# MB1-USB-r1_0.net
KiCad netlist of a schematic drawn in Altium Designer
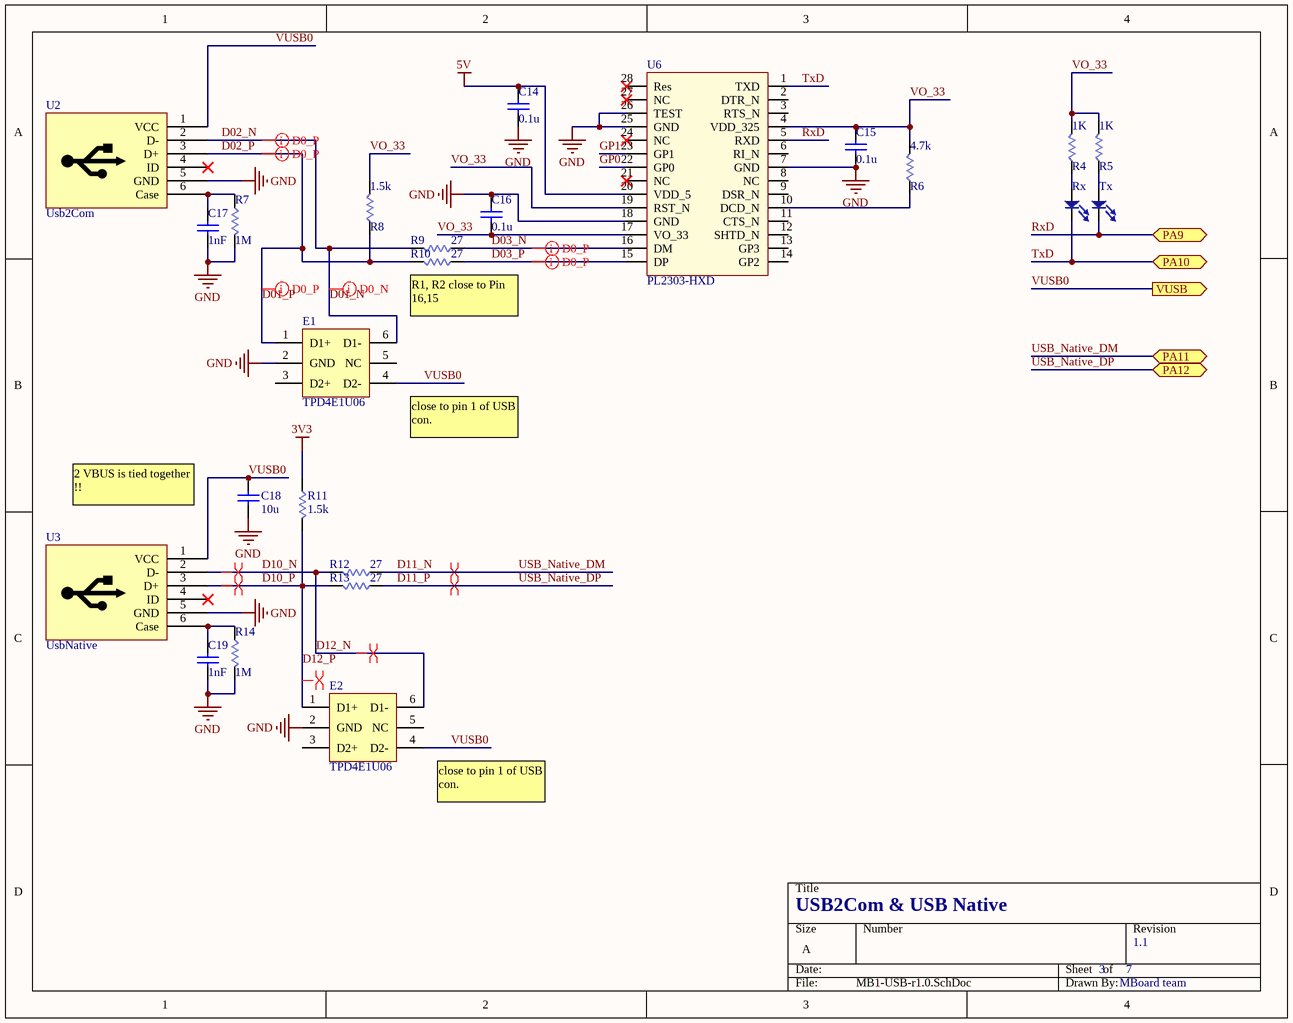
[diagram p0: MB1-USB-r1.0.SchDoc]

(export (version "E")
  (design (tool "Eeschema 10.0.6"))
  (components
    (comp (ref "C14")
      (value "0.1u")
      (footprint "SM_0805_C_CERAMIC")
      (description "Non-polarity ceramic capacitor")
      (fields (field (name "Comment") "CAP Ceramic") (field (name "PUBLISHER") "Altium Limited"))
      (libsource (lib "HLib_schematic_lib") (part "CAP Ceramic"))
    )
    (comp (ref "C15")
      (value "0.1u")
      (footprint "SM_0805_C_CERAMIC")
      (description "Non-polarity ceramic capacitor")
      (fields (field (name "Comment") "CAP Ceramic") (field (name "PUBLISHER") "Altium Limited"))
      (libsource (lib "HLib_schematic_lib") (part "CAP Ceramic"))
    )
    (comp (ref "C16")
      (value "0.1u")
      (footprint "SM_0805_C_CERAMIC")
      (description "Non-polarity ceramic capacitor")
      (fields (field (name "Comment") "CAP Ceramic") (field (name "PUBLISHER") "Altium Limited"))
      (libsource (lib "HLib_schematic_lib") (part "CAP Ceramic"))
    )
    (comp (ref "C17")
      (value "1nF")
      (footprint "SM_0805_C_CERAMIC")
      (description "Non-polarity ceramic capacitor")
      (fields (field (name "Comment") "CAP Ceramic") (field (name "PUBLISHER") "Altium Limited"))
      (libsource (lib "HLib_schematic_lib") (part "CAP Ceramic"))
    )
    (comp (ref "C18")
      (value "10u")
      (footprint "SM_0805_C_CERAMIC")
      (description "Non-polarity ceramic capacitor")
      (fields (field (name "Comment") "CAP Ceramic") (field (name "PUBLISHER") "Altium Limited"))
      (libsource (lib "HLib_schematic_lib") (part "CAP Ceramic"))
    )
    (comp (ref "C19")
      (value "1nF")
      (footprint "SM_0805_C_CERAMIC")
      (description "Non-polarity ceramic capacitor")
      (fields (field (name "Comment") "CAP Ceramic") (field (name "PUBLISHER") "Altium Limited"))
      (libsource (lib "HLib_schematic_lib") (part "CAP Ceramic"))
    )
    (comp (ref "E1") (value "TPD4E1U06") (footprint "SC70-6") (libsource (lib "MyLib") (part "TPD4E1U06")))
    (comp (ref "E2") (value "TPD4E1U06") (footprint "SC70-6") (libsource (lib "MyLib") (part "TPD4E1U06")))
    (comp (ref "R4")
      (value "1K")
      (footprint "SM_0805_R")
      (description "Resistor")
      (fields (field (name "PUBLISHER") "Altium Limited"))
      (libsource (lib "HLib_schematic_lib") (part "R"))
    )
    (comp (ref "R5")
      (value "1K")
      (footprint "SM_0805_R")
      (description "Resistor")
      (fields (field (name "PUBLISHER") "Altium Limited"))
      (libsource (lib "HLib_schematic_lib") (part "R"))
    )
    (comp (ref "R6")
      (value "4.7k")
      (footprint "SM_0805_R")
      (description "Resistor")
      (fields (field (name "PUBLISHER") "Altium Limited"))
      (libsource (lib "HLib_schematic_lib") (part "R"))
    )
    (comp (ref "R7")
      (value "1M")
      (footprint "SM_0805_R")
      (description "Resistor")
      (fields (field (name "PUBLISHER") "Altium Limited"))
      (libsource (lib "HLib_schematic_lib") (part "R"))
    )
    (comp (ref "R8")
      (value "1.5k")
      (footprint "SM_0805_R")
      (description "Resistor")
      (fields (field (name "PUBLISHER") "Altium Limited"))
      (libsource (lib "HLib_schematic_lib") (part "R"))
    )
    (comp (ref "R9")
      (value "27")
      (footprint "SM_0805_R")
      (description "Resistor")
      (fields (field (name "PUBLISHER") "Altium Limited"))
      (libsource (lib "HLib_schematic_lib") (part "R"))
    )
    (comp (ref "R10")
      (value "27")
      (footprint "SM_0805_R")
      (description "Resistor")
      (fields (field (name "PUBLISHER") "Altium Limited"))
      (libsource (lib "HLib_schematic_lib") (part "R"))
    )
    (comp (ref "R11")
      (value "1.5k")
      (footprint "SM_0805_R")
      (description "Resistor")
      (fields (field (name "PUBLISHER") "Altium Limited"))
      (libsource (lib "HLib_schematic_lib") (part "R"))
    )
    (comp (ref "R12")
      (value "27")
      (footprint "SM_0805_R")
      (description "Resistor")
      (fields (field (name "PUBLISHER") "Altium Limited"))
      (libsource (lib "HLib_schematic_lib") (part "R"))
    )
    (comp (ref "R13")
      (value "27")
      (footprint "SM_0805_R")
      (description "Resistor")
      (fields (field (name "PUBLISHER") "Altium Limited"))
      (libsource (lib "HLib_schematic_lib") (part "R"))
    )
    (comp (ref "R14")
      (value "1M")
      (footprint "SM_0805_R")
      (description "Resistor")
      (fields (field (name "PUBLISHER") "Altium Limited"))
      (libsource (lib "HLib_schematic_lib") (part "R"))
    )
    (comp (ref "Rx")
      (value "Blue")
      (footprint "SM_0805_POL_LD")
      (description "LED")
      (fields (field (name "PUBLISHER") "Altium Limited"))
      (libsource (lib "HLib_schematic_lib") (part "LED"))
    )
    (comp (ref "Tx")
      (value "Green")
      (footprint "SM_0805_POL_LD")
      (description "LED")
      (fields (field (name "PUBLISHER") "Altium Limited"))
      (libsource (lib "HLib_schematic_lib") (part "LED"))
    )
    (comp (ref "U2")
      (value "Usb2Com")
      (footprint "USB_Micro_typeB_2")
      (libsource (lib "MyLib") (part "USB-Mini-B"))
    )
    (comp (ref "U3")
      (value "UsbNative")
      (footprint "USB_Micro_typeB_2")
      (libsource (lib "MyLib") (part "USB-Mini-B"))
    )
    (comp (ref "U6") (value "PL2303-HXD") (footprint "SSOP-28") (libsource (lib "MyLib") (part "PL2303-HXD")))
  )
  (nets
    (net (code "1") (name "/D01_N") (class "Default")
      (node (ref "E1") (pin "6") (pinfunction "D1-_6") (pintype "passive"))
      (node (ref "R9") (pin "2") (pinfunction "2_2") (pintype "passive"))
      (node (ref "U2") (pin "2") (pinfunction "D-_2") (pintype "passive"))
    )
    (net (code "2") (name "/D01_P") (class "Default")
      (node (ref "E1") (pin "1") (pinfunction "D1+_1") (pintype "passive"))
      (node (ref "R10") (pin "2") (pinfunction "2_2") (pintype "passive"))
      (node (ref "R8") (pin "1") (pinfunction "1_1") (pintype "passive"))
      (node (ref "U2") (pin "3") (pinfunction "D+_3") (pintype "passive"))
    )
    (net (code "3") (name "/D03_N") (class "Default")
      (node (ref "R9") (pin "1") (pinfunction "1_1") (pintype "passive"))
      (node (ref "U6") (pin "16") (pinfunction "DM_16") (pintype "passive"))
    )
    (net (code "4") (name "/D03_P") (class "Default")
      (node (ref "R10") (pin "1") (pinfunction "1_1") (pintype "passive"))
      (node (ref "U6") (pin "15") (pinfunction "DP_15") (pintype "passive"))
    )
    (net (code "5") (name "/D10_N") (class "Default")
      (node (ref "E2") (pin "6") (pinfunction "D1-_6") (pintype "passive"))
      (node (ref "R12") (pin "2") (pinfunction "2_2") (pintype "passive"))
      (node (ref "U3") (pin "2") (pinfunction "D-_2") (pintype "passive"))
    )
    (net (code "6") (name "/D10_P") (class "Default")
      (node (ref "E2") (pin "1") (pinfunction "D1+_1") (pintype "passive"))
      (node (ref "R11") (pin "2") (pinfunction "2_2") (pintype "passive"))
      (node (ref "R13") (pin "2") (pinfunction "2_2") (pintype "passive"))
      (node (ref "U3") (pin "3") (pinfunction "D+_3") (pintype "passive"))
    )
    (net (code "7") (name "/D11_N") (class "Default")
      (node (ref "R12") (pin "1") (pinfunction "1_1") (pintype "passive"))
    )
    (net (code "8") (name "/D11_P") (class "Default")
      (node (ref "R13") (pin "1") (pinfunction "1_1") (pintype "passive"))
    )
    (net (code "9") (name "/GP0") (class "Default")
      (node (ref "U6") (pin "22") (pinfunction "GP0_22") (pintype "passive"))
    )
    (net (code "10") (name "/GP1") (class "Default")
      (node (ref "U6") (pin "23") (pinfunction "GP1_23") (pintype "passive"))
    )
    (net (code "11") (name "/RxD") (class "Default")
      (node (ref "Tx") (pin "2") (pinfunction "K_2") (pintype "passive"))
      (node (ref "U6") (pin "5") (pinfunction "RXD_5") (pintype "passive"))
    )
    (net (code "12") (name "/TxD") (class "Default")
      (node (ref "Rx") (pin "2") (pinfunction "K_2") (pintype "passive"))
      (node (ref "U6") (pin "1") (pinfunction "TXD_1") (pintype "passive"))
    )
    (net (code "13") (name "/VO_33") (class "Default")
      (node (ref "C15") (pin "2") (pinfunction "2_2") (pintype "passive"))
      (node (ref "C16") (pin "1") (pinfunction "1_1") (pintype "passive"))
      (node (ref "R4") (pin "2") (pinfunction "2_2") (pintype "passive"))
      (node (ref "R5") (pin "2") (pinfunction "2_2") (pintype "passive"))
      (node (ref "R6") (pin "2") (pinfunction "2_2") (pintype "passive"))
      (node (ref "R8") (pin "2") (pinfunction "2_2") (pintype "passive"))
      (node (ref "U6") (pin "17") (pinfunction "VO_33_17") (pintype "passive"))
      (node (ref "U6") (pin "19") (pinfunction "RST_N_19") (pintype "passive"))
      (node (ref "U6") (pin "4") (pinfunction "VDD_325_4") (pintype "passive"))
    )
    (net (code "14") (name "/VUSB0") (class "Default")
      (node (ref "C18") (pin "2") (pinfunction "2_2") (pintype "passive"))
      (node (ref "E1") (pin "4") (pinfunction "D2-_4") (pintype "passive"))
      (node (ref "E2") (pin "4") (pinfunction "D2-_4") (pintype "passive"))
      (node (ref "U2") (pin "1") (pinfunction "VCC_1") (pintype "passive"))
      (node (ref "U3") (pin "1") (pinfunction "VCC_1") (pintype "passive"))
    )
    (net (code "15") (name "3V3") (class "Default")
      (node (ref "R11") (pin "1") (pinfunction "1_1") (pintype "passive"))
    )
    (net (code "16") (name "5V") (class "Default")
      (node (ref "C14") (pin "2") (pinfunction "2_2") (pintype "passive"))
      (node (ref "U6") (pin "20") (pinfunction "VDD_5_20") (pintype "passive"))
    )
    (net (code "17") (name "GND") (class "Default")
      (node (ref "C14") (pin "1") (pinfunction "1_1") (pintype "passive"))
      (node (ref "C15") (pin "1") (pinfunction "1_1") (pintype "passive"))
      (node (ref "C16") (pin "2") (pinfunction "2_2") (pintype "passive"))
      (node (ref "C17") (pin "1") (pinfunction "1_1") (pintype "passive"))
      (node (ref "C18") (pin "1") (pinfunction "1_1") (pintype "passive"))
      (node (ref "C19") (pin "1") (pinfunction "1_1") (pintype "passive"))
      (node (ref "E1") (pin "2") (pinfunction "GND_2") (pintype "passive"))
      (node (ref "E2") (pin "2") (pinfunction "GND_2") (pintype "passive"))
      (node (ref "R14") (pin "2") (pinfunction "2_2") (pintype "passive"))
      (node (ref "R7") (pin "2") (pinfunction "2_2") (pintype "passive"))
      (node (ref "U2") (pin "5") (pinfunction "GND_5") (pintype "passive"))
      (node (ref "U3") (pin "5") (pinfunction "GND_5") (pintype "passive"))
      (node (ref "U6") (pin "18") (pinfunction "GND_18") (pintype "passive"))
      (node (ref "U6") (pin "25") (pinfunction "GND_25") (pintype "passive"))
      (node (ref "U6") (pin "26") (pinfunction "TEST_26") (pintype "passive"))
      (node (ref "U6") (pin "7") (pinfunction "GND_7") (pintype "passive"))
    )
    (net (code "18") (name "Net-(Rx-A)") (class "Default")
      (node (ref "R4") (pin "1") (pinfunction "1_1") (pintype "passive"))
      (node (ref "Rx") (pin "1") (pinfunction "A_1") (pintype "passive"))
    )
    (net (code "19") (name "Net-(Tx-A)") (class "Default")
      (node (ref "R5") (pin "1") (pinfunction "1_1") (pintype "passive"))
      (node (ref "Tx") (pin "1") (pinfunction "A_1") (pintype "passive"))
    )
    (net (code "20") (name "Net-(U2-Case)") (class "Default")
      (node (ref "C17") (pin "2") (pinfunction "2_2") (pintype "passive"))
      (node (ref "R7") (pin "1") (pinfunction "1_1") (pintype "passive"))
      (node (ref "U2") (pin "6") (pinfunction "Case_6") (pintype "power_in"))
    )
    (net (code "21") (name "Net-(U3-Case)") (class "Default")
      (node (ref "C19") (pin "2") (pinfunction "2_2") (pintype "passive"))
      (node (ref "R14") (pin "1") (pinfunction "1_1") (pintype "passive"))
      (node (ref "U3") (pin "6") (pinfunction "Case_6") (pintype "power_in"))
    )
    (net (code "22") (name "Net-(U6-DCD_N)") (class "Default")
      (node (ref "R6") (pin "1") (pinfunction "1_1") (pintype "passive"))
      (node (ref "U6") (pin "10") (pinfunction "DCD_N_10") (pintype "passive"))
    )
    (net (code "23") (name "unconnected-(E1-D2+-Pad3)") (class "Default")
      (node (ref "E1") (pin "3") (pinfunction "D2+_3") (pintype "passive"))
    )
    (net (code "24") (name "unconnected-(E1-NC-Pad5)") (class "Default")
      (node (ref "E1") (pin "5") (pinfunction "NC_5") (pintype "passive"))
    )
    (net (code "25") (name "unconnected-(E2-D2+-Pad3)") (class "Default")
      (node (ref "E2") (pin "3") (pinfunction "D2+_3") (pintype "passive"))
    )
    (net (code "26") (name "unconnected-(E2-NC-Pad5)") (class "Default")
      (node (ref "E2") (pin "5") (pinfunction "NC_5") (pintype "passive"))
    )
    (net (code "27") (name "unconnected-(U2-ID-Pad4)") (class "Default")
      (node (ref "U2") (pin "4") (pinfunction "ID_4") (pintype "passive+no_connect"))
    )
    (net (code "28") (name "unconnected-(U3-ID-Pad4)") (class "Default")
      (node (ref "U3") (pin "4") (pinfunction "ID_4") (pintype "passive+no_connect"))
    )
    (net (code "29") (name "unconnected-(U6-CTS_N-Pad11)") (class "Default")
      (node (ref "U6") (pin "11") (pinfunction "CTS_N_11") (pintype "passive"))
    )
    (net (code "30") (name "unconnected-(U6-DSR_N-Pad9)") (class "Default")
      (node (ref "U6") (pin "9") (pinfunction "DSR_N_9") (pintype "passive"))
    )
    (net (code "31") (name "unconnected-(U6-DTR_N-Pad2)") (class "Default")
      (node (ref "U6") (pin "2") (pinfunction "DTR_N_2") (pintype "passive"))
    )
    (net (code "32") (name "unconnected-(U6-GP2-Pad14)") (class "Default")
      (node (ref "U6") (pin "14") (pinfunction "GP2_14") (pintype "passive"))
    )
    (net (code "33") (name "unconnected-(U6-GP3-Pad13)") (class "Default")
      (node (ref "U6") (pin "13") (pinfunction "GP3_13") (pintype "passive"))
    )
    (net (code "34") (name "unconnected-(U6-NC-Pad8)") (class "Default")
      (node (ref "U6") (pin "8") (pinfunction "NC_8") (pintype "passive"))
    )
    (net (code "35") (name "unconnected-(U6-NC-Pad21)") (class "Default")
      (node (ref "U6") (pin "21") (pinfunction "NC_21") (pintype "passive+no_connect"))
    )
    (net (code "36") (name "unconnected-(U6-NC-Pad24)") (class "Default")
      (node (ref "U6") (pin "24") (pinfunction "NC_24") (pintype "passive+no_connect"))
    )
    (net (code "37") (name "unconnected-(U6-NC-Pad27)") (class "Default")
      (node (ref "U6") (pin "27") (pinfunction "NC_27") (pintype "passive+no_connect"))
    )
    (net (code "38") (name "unconnected-(U6-RI_N-Pad6)") (class "Default")
      (node (ref "U6") (pin "6") (pinfunction "RI_N_6") (pintype "passive"))
    )
    (net (code "39") (name "unconnected-(U6-RTS_N-Pad3)") (class "Default")
      (node (ref "U6") (pin "3") (pinfunction "RTS_N_3") (pintype "passive"))
    )
    (net (code "40") (name "unconnected-(U6-Res-Pad28)") (class "Default")
      (node (ref "U6") (pin "28") (pinfunction "Res_28") (pintype "passive+no_connect"))
    )
    (net (code "41") (name "unconnected-(U6-SHTD_N-Pad12)") (class "Default")
      (node (ref "U6") (pin "12") (pinfunction "SHTD_N_12") (pintype "passive"))
    )
  )
)
